# DualMonoPSU4.net
KiCad netlist of a schematic drawn in EAGLE
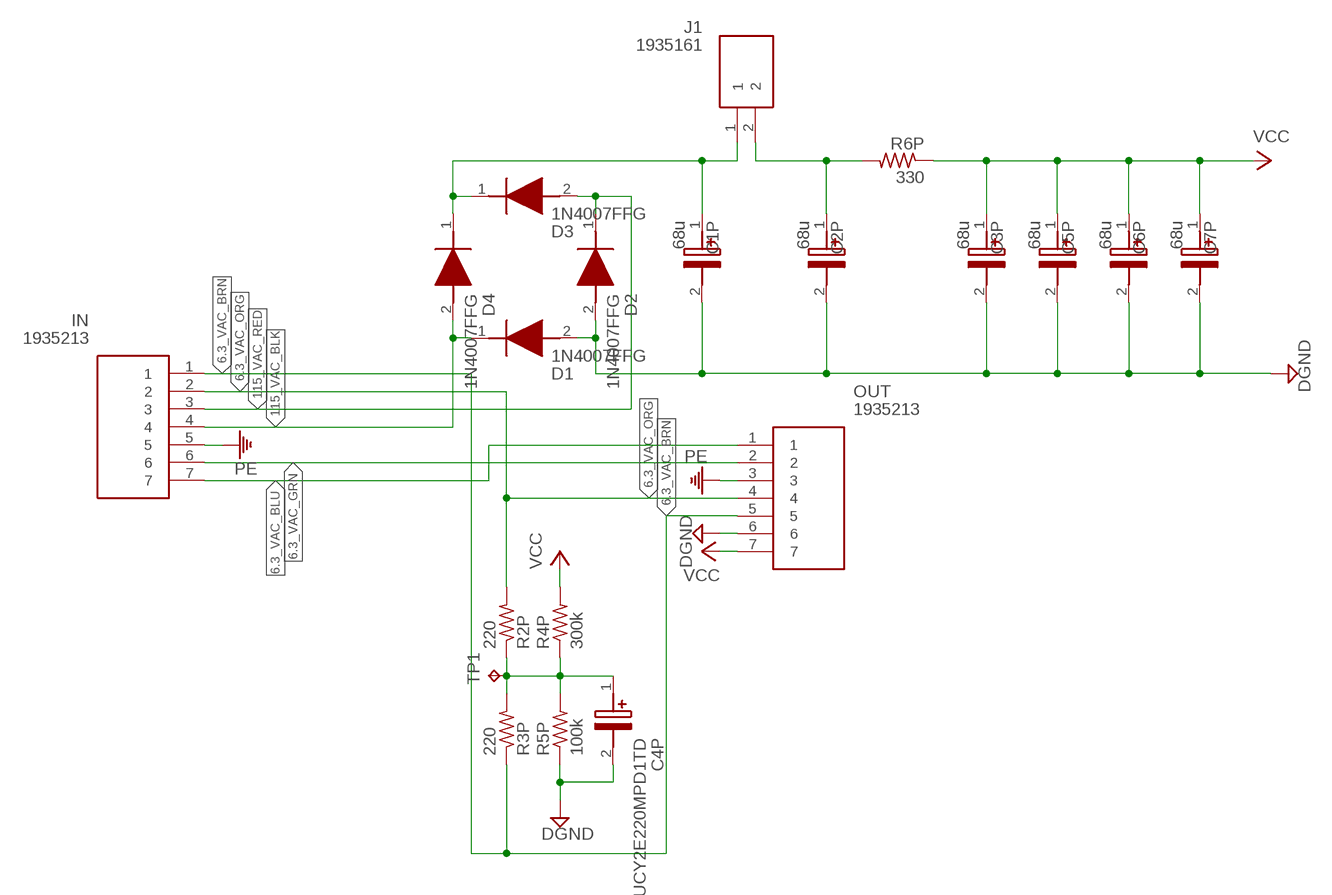
[diagram p0: schematic, sheet 1]

(export (version "E")
  (design (tool "Eeschema 10.0.6"))
  (components
    (comp (ref "C1P")
      (value "68u")
      (footprint "eagle-import:CAPPRD750W80D1475H4700")
      (fields (field (name "MANUFACTURER_PART_NUMBER") "500HXW68MEFR14.5X45"))
      (libsource (lib "eagle-import") (part "500HXW68MEFR14.5X45"))
    )
    (comp (ref "C2P")
      (value "68u")
      (footprint "eagle-import:CAPPRD750W80D1475H4700")
      (fields (field (name "MANUFACTURER_PART_NUMBER") "500HXW68MEFR14.5X45"))
      (libsource (lib "eagle-import") (part "500HXW68MEFR14.5X45"))
    )
    (comp (ref "C3P")
      (value "68u")
      (footprint "eagle-import:CAPPRD750W80D1475H4700")
      (fields (field (name "MANUFACTURER_PART_NUMBER") "500HXW68MEFR14.5X45"))
      (libsource (lib "eagle-import") (part "500HXW68MEFR14.5X45"))
    )
    (comp (ref "C4P")
      (value "UCY2E220MPD1TD")
      (footprint "eagle-import:CAPPRD500W60D1025H1750")
      (fields (field (name "MOUSER_PART_NUMBER") "647-UCY2E220MPD1TD"))
      (libsource (lib "eagle-import") (part "UCY2E220MPD1TD"))
    )
    (comp (ref "C5P")
      (value "68u")
      (footprint "eagle-import:CAPPRD750W80D1475H4700")
      (fields (field (name "MANUFACTURER_PART_NUMBER") "500HXW68MEFR14.5X45"))
      (libsource (lib "eagle-import") (part "500HXW68MEFR14.5X45"))
    )
    (comp (ref "C6P")
      (value "68u")
      (footprint "eagle-import:CAPPRD750W80D1475H4700")
      (fields (field (name "MANUFACTURER_PART_NUMBER") "500HXW68MEFR14.5X45"))
      (libsource (lib "eagle-import") (part "500HXW68MEFR14.5X45"))
    )
    (comp (ref "C7P")
      (value "68u")
      (footprint "eagle-import:CAPPRD750W80D1475H4700")
      (fields (field (name "MANUFACTURER_PART_NUMBER") "500HXW68MEFR14.5X45"))
      (libsource (lib "eagle-import") (part "500HXW68MEFR14.5X45"))
    )
    (comp (ref "D1")
      (value "1N4007FFG")
      (footprint "eagle-import:DIOAD1405W86L465D235")
      (fields (field (name "MOUSER_PART_NUMBER") "863-1N4007FFG"))
      (libsource (lib "eagle-import") (part "1N4007FFG"))
    )
    (comp (ref "D2")
      (value "1N4007FFG")
      (footprint "eagle-import:DIOAD1405W86L465D235")
      (fields (field (name "MOUSER_PART_NUMBER") "863-1N4007FFG"))
      (libsource (lib "eagle-import") (part "1N4007FFG"))
    )
    (comp (ref "D3")
      (value "1N4007FFG")
      (footprint "eagle-import:DIOAD1405W86L465D235")
      (fields (field (name "MOUSER_PART_NUMBER") "863-1N4007FFG"))
      (libsource (lib "eagle-import") (part "1N4007FFG"))
    )
    (comp (ref "D4")
      (value "1N4007FFG")
      (footprint "eagle-import:DIOAD1405W86L465D235")
      (fields (field (name "MOUSER_PART_NUMBER") "863-1N4007FFG"))
      (libsource (lib "eagle-import") (part "1N4007FFG"))
    )
    (comp (ref "IN")
      (value "1935213")
      (footprint "eagle-import:1935213")
      (fields (field (name "MOUSER_PART_NUMBER") "651-1935213"))
      (libsource (lib "eagle-import") (part "1935213"))
    )
    (comp (ref "J1")
      (value "1935161")
      (footprint "eagle-import:1935161")
      (fields (field (name "MOUSER_PART_NUMBER") "651-1935161"))
      (libsource (lib "eagle-import") (part "1935161"))
    )
    (comp (ref "OUT")
      (value "1935213")
      (footprint "eagle-import:1935213")
      (fields (field (name "MOUSER_PART_NUMBER") "651-1935213"))
      (libsource (lib "eagle-import") (part "1935213"))
    )
    (comp (ref "R2P")
      (value "220")
      (footprint "eagle-import:0411_15")
      (libsource (lib "eagle-import") (part "R-US_0411/15"))
    )
    (comp (ref "R3P")
      (value "220")
      (footprint "eagle-import:0411_15")
      (libsource (lib "eagle-import") (part "R-US_0411/15"))
    )
    (comp (ref "R4P")
      (value "300k")
      (footprint "eagle-import:0411_15")
      (libsource (lib "eagle-import") (part "R-US_0411/15"))
    )
    (comp (ref "R5P")
      (value "100k")
      (footprint "eagle-import:0411_15")
      (libsource (lib "eagle-import") (part "R-US_0411/15"))
    )
    (comp (ref "R6P")
      (value "330")
      (footprint "eagle-import:0411_15")
      (libsource (lib "eagle-import") (part "R-US_0411/15"))
    )
    (comp (ref "TP1")
      (value "TPB2,54")
      (footprint "eagle-import:B2,54")
      (libsource (lib "eagle-import") (part "TPB2,54"))
    )
  )
  (nets
    (net (code "1") (name "6.3_VAC_BLU") (class "Default")
      (node (ref "IN") (pin "7") (pinfunction "7_7") (pintype "bidirectional"))
      (node (ref "OUT") (pin "1") (pinfunction "1_1") (pintype "bidirectional"))
    )
    (net (code "2") (name "6.3_VAC_BRN") (class "Default")
      (node (ref "IN") (pin "1") (pinfunction "1_1") (pintype "bidirectional"))
      (node (ref "OUT") (pin "5") (pinfunction "5_5") (pintype "bidirectional"))
      (node (ref "R3P") (pin "1") (pinfunction "1_1") (pintype "passive"))
    )
    (net (code "3") (name "6.3_VAC_GRN") (class "Default")
      (node (ref "IN") (pin "6") (pinfunction "6_6") (pintype "bidirectional"))
      (node (ref "OUT") (pin "2") (pinfunction "2_2") (pintype "bidirectional"))
    )
    (net (code "4") (name "6.3_VAC_ORG") (class "Default")
      (node (ref "IN") (pin "2") (pinfunction "2_2") (pintype "bidirectional"))
      (node (ref "OUT") (pin "4") (pinfunction "4_4") (pintype "bidirectional"))
      (node (ref "R2P") (pin "2") (pinfunction "2_2") (pintype "passive"))
    )
    (net (code "5") (name "115_VAC_BLK") (class "Default")
      (node (ref "D1") (pin "1") (pinfunction "K_1") (pintype "bidirectional"))
      (node (ref "D4") (pin "2") (pinfunction "A_2") (pintype "bidirectional"))
      (node (ref "IN") (pin "4") (pinfunction "4_4") (pintype "bidirectional"))
    )
    (net (code "6") (name "115_VAC_RED") (class "Default")
      (node (ref "D2") (pin "1") (pinfunction "K_1") (pintype "bidirectional"))
      (node (ref "D3") (pin "2") (pinfunction "A_2") (pintype "bidirectional"))
      (node (ref "IN") (pin "3") (pinfunction "3_3") (pintype "bidirectional"))
    )
    (net (code "7") (name "DGND") (class "Default")
      (node (ref "C1P") (pin "2") (pinfunction "-_2") (pintype "bidirectional"))
      (node (ref "C2P") (pin "2") (pinfunction "-_2") (pintype "bidirectional"))
      (node (ref "C3P") (pin "2") (pinfunction "-_2") (pintype "bidirectional"))
      (node (ref "C4P") (pin "2") (pinfunction "-_2") (pintype "bidirectional"))
      (node (ref "C5P") (pin "2") (pinfunction "-_2") (pintype "bidirectional"))
      (node (ref "C6P") (pin "2") (pinfunction "-_2") (pintype "bidirectional"))
      (node (ref "C7P") (pin "2") (pinfunction "-_2") (pintype "bidirectional"))
      (node (ref "D1") (pin "2") (pinfunction "A_2") (pintype "bidirectional"))
      (node (ref "D2") (pin "2") (pinfunction "A_2") (pintype "bidirectional"))
      (node (ref "OUT") (pin "6") (pinfunction "6_6") (pintype "bidirectional"))
      (node (ref "R5P") (pin "1") (pinfunction "1_1") (pintype "passive"))
    )
    (net (code "8") (name "Net-(C1P-+)") (class "Default")
      (node (ref "C1P") (pin "1") (pinfunction "+_1") (pintype "bidirectional"))
      (node (ref "D3") (pin "1") (pinfunction "K_1") (pintype "bidirectional"))
      (node (ref "D4") (pin "1") (pinfunction "K_1") (pintype "bidirectional"))
      (node (ref "J1") (pin "1") (pinfunction "1_1") (pintype "bidirectional"))
    )
    (net (code "9") (name "Net-(C2P-+)") (class "Default")
      (node (ref "C2P") (pin "1") (pinfunction "+_1") (pintype "bidirectional"))
      (node (ref "J1") (pin "2") (pinfunction "2_2") (pintype "bidirectional"))
      (node (ref "R6P") (pin "2") (pinfunction "2_2") (pintype "passive"))
    )
    (net (code "10") (name "Net-(C4P-+)") (class "Default")
      (node (ref "C4P") (pin "1") (pinfunction "+_1") (pintype "bidirectional"))
      (node (ref "R2P") (pin "1") (pinfunction "1_1") (pintype "passive"))
      (node (ref "R3P") (pin "2") (pinfunction "2_2") (pintype "passive"))
      (node (ref "R4P") (pin "1") (pinfunction "1_1") (pintype "passive"))
      (node (ref "R5P") (pin "2") (pinfunction "2_2") (pintype "passive"))
      (node (ref "TP1") (pin "TP") (pinfunction "TP_TP") (pintype "input"))
    )
    (net (code "11") (name "PE") (class "Default")
      (node (ref "IN") (pin "5") (pinfunction "5_5") (pintype "bidirectional"))
      (node (ref "OUT") (pin "3") (pinfunction "3_3") (pintype "bidirectional"))
    )
    (net (code "12") (name "VCC") (class "Default")
      (node (ref "C3P") (pin "1") (pinfunction "+_1") (pintype "bidirectional"))
      (node (ref "C5P") (pin "1") (pinfunction "+_1") (pintype "bidirectional"))
      (node (ref "C6P") (pin "1") (pinfunction "+_1") (pintype "bidirectional"))
      (node (ref "C7P") (pin "1") (pinfunction "+_1") (pintype "bidirectional"))
      (node (ref "OUT") (pin "7") (pinfunction "7_7") (pintype "bidirectional"))
      (node (ref "R4P") (pin "2") (pinfunction "2_2") (pintype "passive"))
      (node (ref "R6P") (pin "1") (pinfunction "1_1") (pintype "passive"))
    )
  )
)
